# Controlboard.net
KiCad netlist of a schematic drawn in EAGLE
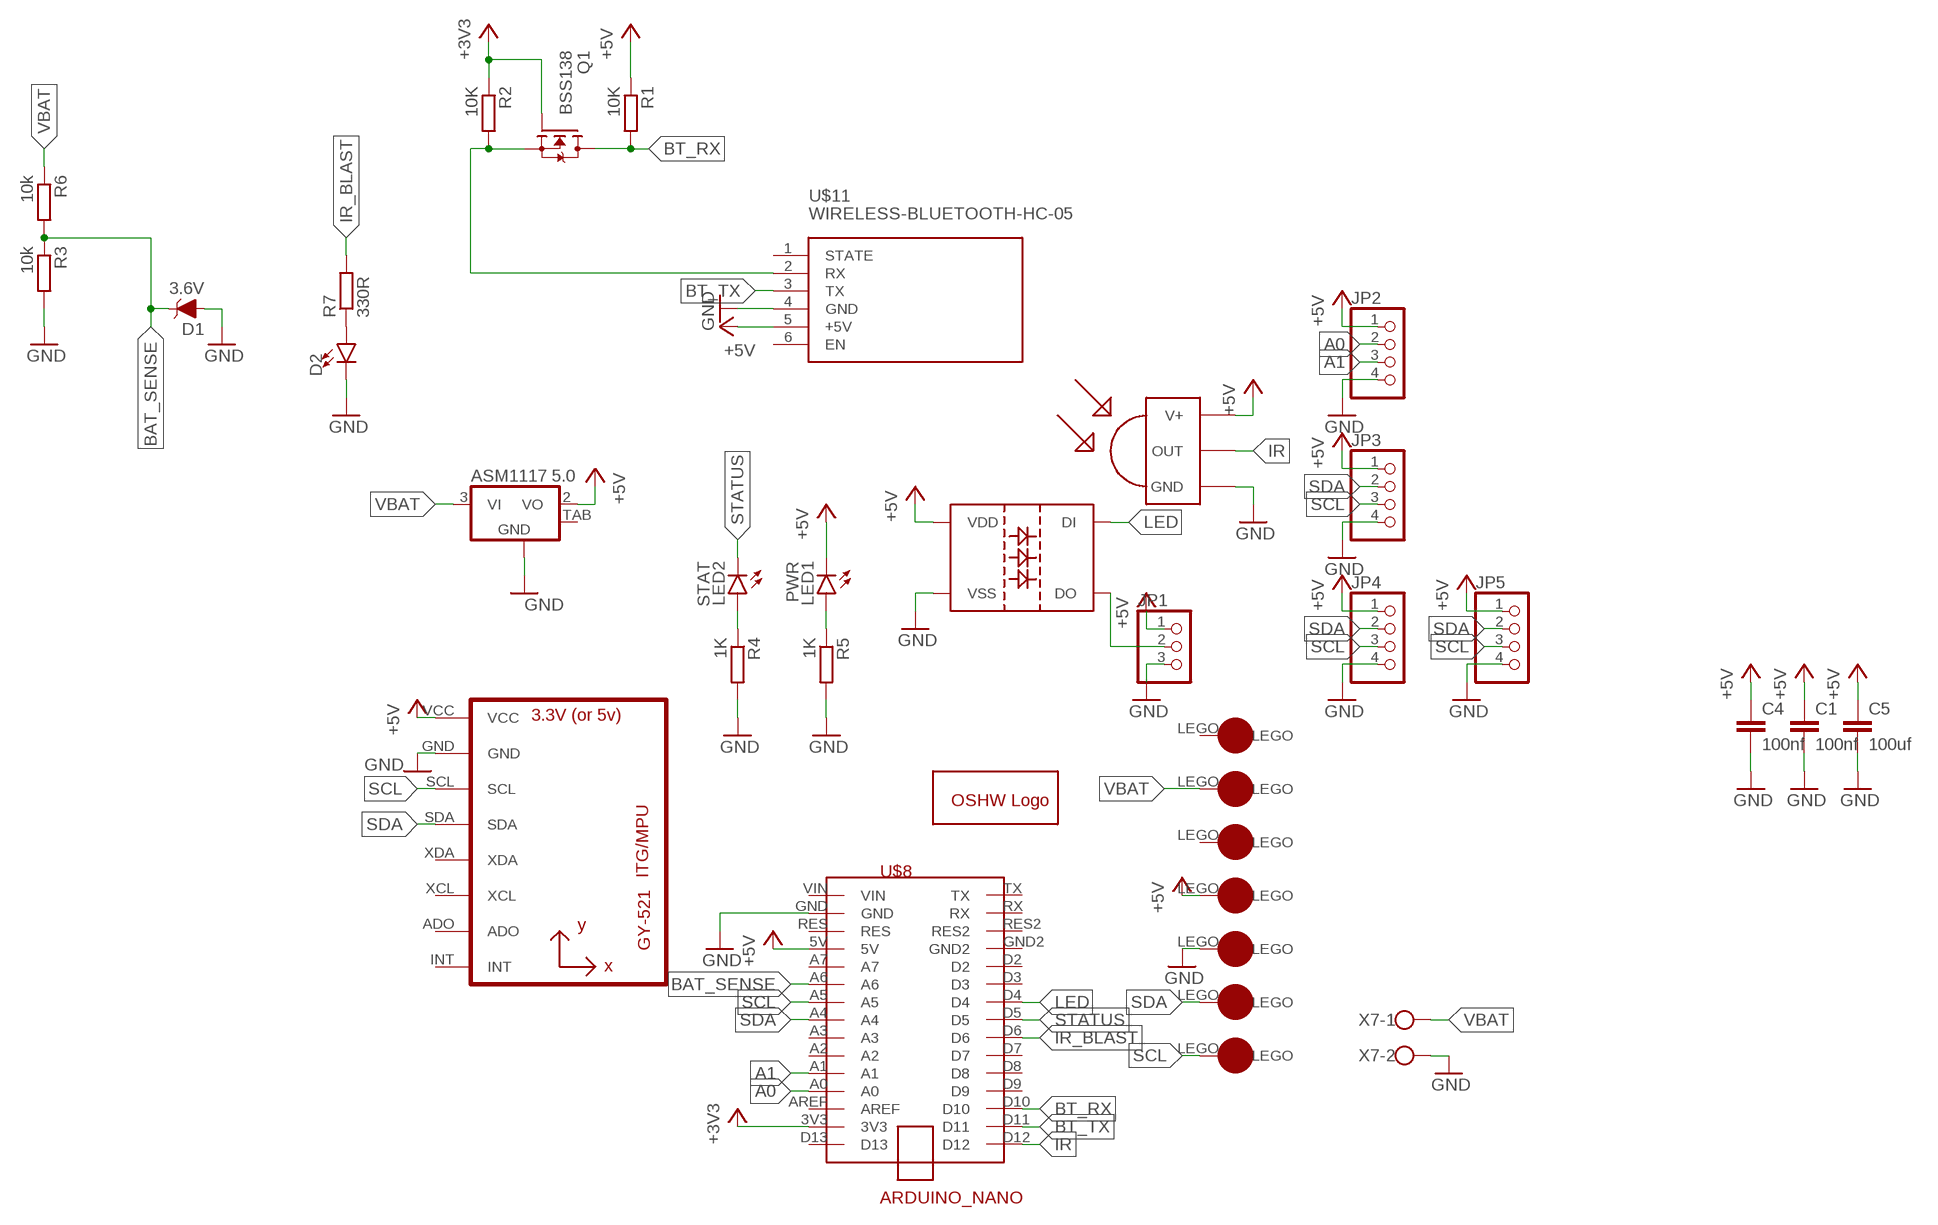
[diagram p0: schematic, sheet 1]

(export (version "E")
  (design (tool "Eeschema 10.0.6"))
  (components
    (comp (ref "C1")
      (value "100nf")
      (footprint "eagle-import:C1206")
      (libsource (lib "eagle-import") (part "C-EUC1206"))
    )
    (comp (ref "C4")
      (value "100nf")
      (footprint "eagle-import:C1206")
      (libsource (lib "eagle-import") (part "C-EUC1206"))
    )
    (comp (ref "C5")
      (value "100uf")
      (footprint "eagle-import:C1206")
      (libsource (lib "eagle-import") (part "C-EUC1206"))
    )
    (comp (ref "D1")
      (value "3.6V")
      (footprint "eagle-import:SOD-323")
      (libsource (lib "eagle-import") (part "DIODE-ZENER-BZT52C3V6S"))
    )
    (comp (ref "D2")
      (value "LED5MM")
      (footprint "eagle-import:LED_5MM")
      (libsource (lib "eagle-import") (part "LED5MM"))
    )
    (comp (ref "JP1")
      (value "PINHD-1X3")
      (footprint "eagle-import:1X03")
      (libsource (lib "eagle-import") (part "PINHD-1X3"))
    )
    (comp (ref "JP2")
      (value "PINHD-1X4")
      (footprint "eagle-import:1X04")
      (libsource (lib "eagle-import") (part "PINHD-1X4"))
    )
    (comp (ref "JP3")
      (value "PINHD-1X4")
      (footprint "eagle-import:1X04")
      (libsource (lib "eagle-import") (part "PINHD-1X4"))
    )
    (comp (ref "JP4")
      (value "PINHD-1X4")
      (footprint "eagle-import:1X04")
      (libsource (lib "eagle-import") (part "PINHD-1X4"))
    )
    (comp (ref "JP5")
      (value "PINHD-1X4")
      (footprint "eagle-import:1X04")
      (libsource (lib "eagle-import") (part "PINHD-1X4"))
    )
    (comp (ref "LED1")
      (value "PWR")
      (footprint "eagle-import:1206")
      (libsource (lib "eagle-import") (part "LEDSMT1206"))
    )
    (comp (ref "LED2")
      (value "STAT")
      (footprint "eagle-import:1206")
      (libsource (lib "eagle-import") (part "LEDSMT1206"))
    )
    (comp (ref "LED3")
      (value "IND")
      (footprint "eagle-import:WS2812B")
      (libsource (lib "eagle-import") (part "WS2812B"))
    )
    (comp (ref "Q1")
      (value "BSS138")
      (footprint "eagle-import:SOT23")
      (fields (field (name "MF") "Fairchild"))
      (libsource (lib "eagle-import") (part "BSS138"))
    )
    (comp (ref "R1")
      (value "10K")
      (footprint "eagle-import:M1206")
      (libsource (lib "eagle-import") (part "R-EU_M1206"))
    )
    (comp (ref "R2")
      (value "10K")
      (footprint "eagle-import:M1206")
      (libsource (lib "eagle-import") (part "R-EU_M1206"))
    )
    (comp (ref "R3")
      (value "10k")
      (footprint "eagle-import:M1206")
      (libsource (lib "eagle-import") (part "R-EU_M1206"))
    )
    (comp (ref "R4")
      (value "1K")
      (footprint "eagle-import:M1206")
      (libsource (lib "eagle-import") (part "R-EU_M1206"))
    )
    (comp (ref "R5")
      (value "1K")
      (footprint "eagle-import:M1206")
      (libsource (lib "eagle-import") (part "R-EU_M1206"))
    )
    (comp (ref "R6")
      (value "10k")
      (footprint "eagle-import:M1206")
      (libsource (lib "eagle-import") (part "R-EU_M1206"))
    )
    (comp (ref "R7")
      (value "330R")
      (footprint "eagle-import:M1206")
      (libsource (lib "eagle-import") (part "R-EU_M1206"))
    )
    (comp (ref "U$1")
      (value "LEGO-1X1")
      (footprint "eagle-import:LEGO-1X1")
      (libsource (lib "eagle-import") (part "LEGO-1X1"))
    )
    (comp (ref "U$2")
      (value "OPENSOURCE")
      (footprint "eagle-import:OSHW_5MM")
      (libsource (lib "eagle-import") (part "OPENSOURCE"))
    )
    (comp (ref "U$3")
      (value "LEGO-1X1")
      (footprint "eagle-import:LEGO-1X1")
      (libsource (lib "eagle-import") (part "LEGO-1X1"))
    )
    (comp (ref "U$4")
      (value "LEGO-1X1")
      (footprint "eagle-import:LEGO-1X1")
      (libsource (lib "eagle-import") (part "LEGO-1X1"))
    )
    (comp (ref "U$5")
      (value "LEGO-1X1")
      (footprint "eagle-import:LEGO-1X1")
      (libsource (lib "eagle-import") (part "LEGO-1X1"))
    )
    (comp (ref "U$6")
      (value "LEGO-1X1")
      (footprint "eagle-import:LEGO-1X1")
      (libsource (lib "eagle-import") (part "LEGO-1X1"))
    )
    (comp (ref "U$7")
      (value "LEGO-1X1")
      (footprint "eagle-import:LEGO-1X1")
      (libsource (lib "eagle-import") (part "LEGO-1X1"))
    )
    (comp (ref "U$8")
      (value "ARDUINO_NANO")
      (footprint "eagle-import:ARDUIN_NANO")
      (libsource (lib "eagle-import") (part "ARDUINO_NANO"))
    )
    (comp (ref "U$9")
      (value "LEGO-1X1")
      (footprint "eagle-import:LEGO-1X1")
      (libsource (lib "eagle-import") (part "LEGO-1X1"))
    )
    (comp (ref "U$10")
      (value "TSOP4838")
      (footprint "eagle-import:TSOP18XX")
      (libsource (lib "eagle-import") (part "TSOP4838"))
    )
    (comp (ref "U$11")
      (value "WIRELESS-BLUETOOTH-HC-05")
      (footprint "eagle-import:WIRELESS-BLUETOOTH-HC-05")
      (libsource (lib "eagle-import") (part "WIRELESS-BLUETOOTH-HC-05"))
    )
    (comp (ref "U$12")
      (value "ASM1117 5.0")
      (footprint "eagle-import:LM1117")
      (libsource (lib "eagle-import") (part "LM1117"))
    )
    (comp (ref "U1")
      (value "MPU-6050MPU6050")
      (footprint "eagle-import:MPU-6050")
      (libsource (lib "eagle-import") (part "MPU-6050MPU6050"))
    )
    (comp (ref "X7")
      (value "W237-102")
      (footprint "eagle-import:W237-102")
      (fields (field (name "MPN") "237-102"))
      (libsource (lib "eagle-import") (part "W237-102"))
    )
  )
  (nets
    (net (code "1") (name "+3V3") (class "Default")
      (node (ref "Q1") (pin "1") (pinfunction "G_1") (pintype "passive"))
      (node (ref "R2") (pin "1") (pinfunction "1_1") (pintype "passive"))
      (node (ref "U$8") (pin "3V3") (pinfunction "3V3_3V3") (pintype "bidirectional"))
    )
    (net (code "2") (name "+5V") (class "Default")
      (node (ref "C1") (pin "1") (pinfunction "1_1") (pintype "passive"))
      (node (ref "C4") (pin "1") (pinfunction "1_1") (pintype "passive"))
      (node (ref "C5") (pin "1") (pinfunction "1_1") (pintype "passive"))
      (node (ref "JP1") (pin "1") (pinfunction "1_1") (pintype "passive"))
      (node (ref "JP2") (pin "1") (pinfunction "1_1") (pintype "passive"))
      (node (ref "JP3") (pin "1") (pinfunction "1_1") (pintype "passive"))
      (node (ref "JP4") (pin "1") (pinfunction "1_1") (pintype "passive"))
      (node (ref "JP5") (pin "1") (pinfunction "1_1") (pintype "passive"))
      (node (ref "LED1") (pin "C") (pinfunction "C_C") (pintype "passive"))
      (node (ref "LED3") (pin "1") (pinfunction "VDD_1") (pintype "bidirectional"))
      (node (ref "R1") (pin "1") (pinfunction "1_1") (pintype "passive"))
      (node (ref "U$10") (pin "VCC") (pinfunction "V+_VCC") (pintype "bidirectional"))
      (node (ref "U$11") (pin "5") (pinfunction "+5V_5") (pintype "power_in"))
      (node (ref "U$12") (pin "2") (pinfunction "VO_2") (pintype "passive"))
      (node (ref "U$5") (pin "LEGO") (pinfunction "LEGO_LEGO") (pintype "bidirectional"))
      (node (ref "U$8") (pin "5V") (pinfunction "5V_5V") (pintype "bidirectional"))
      (node (ref "U1") (pin "VCC") (pinfunction "VCC_VCC") (pintype "bidirectional"))
    )
    (net (code "3") (name "A0") (class "Default")
      (node (ref "JP2") (pin "2") (pinfunction "2_2") (pintype "passive"))
      (node (ref "U$8") (pin "A0") (pinfunction "A0_A0") (pintype "bidirectional"))
    )
    (net (code "4") (name "A1") (class "Default")
      (node (ref "JP2") (pin "3") (pinfunction "3_3") (pintype "passive"))
      (node (ref "U$8") (pin "A1") (pinfunction "A1_A1") (pintype "bidirectional"))
    )
    (net (code "5") (name "BAT_SENSE") (class "Default")
      (node (ref "D1") (pin "C") (pinfunction "C_C") (pintype "passive"))
      (node (ref "R3") (pin "1") (pinfunction "1_1") (pintype "passive"))
      (node (ref "R6") (pin "2") (pinfunction "2_2") (pintype "passive"))
      (node (ref "U$8") (pin "A6") (pinfunction "A6_A6") (pintype "bidirectional"))
    )
    (net (code "6") (name "BT_RX") (class "Default")
      (node (ref "Q1") (pin "3") (pinfunction "D_3") (pintype "passive"))
      (node (ref "R1") (pin "2") (pinfunction "2_2") (pintype "passive"))
      (node (ref "U$8") (pin "D10") (pinfunction "D10_D10") (pintype "bidirectional"))
    )
    (net (code "7") (name "BT_TX") (class "Default")
      (node (ref "U$11") (pin "3") (pinfunction "TX_3") (pintype "bidirectional"))
      (node (ref "U$8") (pin "D11") (pinfunction "D11_D11") (pintype "bidirectional"))
    )
    (net (code "8") (name "GND") (class "Default")
      (node (ref "C1") (pin "2") (pinfunction "2_2") (pintype "passive"))
      (node (ref "C4") (pin "2") (pinfunction "2_2") (pintype "passive"))
      (node (ref "C5") (pin "2") (pinfunction "2_2") (pintype "passive"))
      (node (ref "D1") (pin "A") (pinfunction "A_A") (pintype "passive"))
      (node (ref "D2") (pin "K") (pinfunction "C_K") (pintype "passive"))
      (node (ref "JP1") (pin "3") (pinfunction "3_3") (pintype "passive"))
      (node (ref "JP2") (pin "4") (pinfunction "4_4") (pintype "passive"))
      (node (ref "JP3") (pin "4") (pinfunction "4_4") (pintype "passive"))
      (node (ref "JP4") (pin "4") (pinfunction "4_4") (pintype "passive"))
      (node (ref "JP5") (pin "4") (pinfunction "4_4") (pintype "passive"))
      (node (ref "LED3") (pin "3") (pinfunction "VSS_3") (pintype "bidirectional"))
      (node (ref "R3") (pin "2") (pinfunction "2_2") (pintype "passive"))
      (node (ref "R4") (pin "2") (pinfunction "2_2") (pintype "passive"))
      (node (ref "R5") (pin "2") (pinfunction "2_2") (pintype "passive"))
      (node (ref "U$10") (pin "GND") (pinfunction "GND_GND") (pintype "bidirectional"))
      (node (ref "U$11") (pin "4") (pinfunction "GND_4") (pintype "power_in"))
      (node (ref "U$12") (pin "1") (pinfunction "GND_1") (pintype "passive"))
      (node (ref "U$4") (pin "LEGO") (pinfunction "LEGO_LEGO") (pintype "bidirectional"))
      (node (ref "U$8") (pin "GND") (pinfunction "GND_GND") (pintype "bidirectional"))
      (node (ref "U1") (pin "GND") (pinfunction "GND_GND") (pintype "bidirectional"))
      (node (ref "X7") (pin "2") (pinfunction "KL_2") (pintype "passive"))
    )
    (net (code "9") (name "IR") (class "Default")
      (node (ref "U$10") (pin "OUT") (pinfunction "OUT_OUT") (pintype "bidirectional"))
      (node (ref "U$8") (pin "D12") (pinfunction "D12_D12") (pintype "bidirectional"))
    )
    (net (code "10") (name "IR_BLAST") (class "Default")
      (node (ref "R7") (pin "2") (pinfunction "2_2") (pintype "passive"))
      (node (ref "U$8") (pin "D6") (pinfunction "D6_D6") (pintype "bidirectional"))
    )
    (net (code "11") (name "LED") (class "Default")
      (node (ref "LED3") (pin "4") (pinfunction "DI_4") (pintype "bidirectional"))
      (node (ref "U$8") (pin "D4") (pinfunction "D4_D4") (pintype "bidirectional"))
    )
    (net (code "12") (name "Net-(D2-PadA)") (class "Default")
      (node (ref "D2") (pin "A") (pinfunction "A_A") (pintype "passive"))
      (node (ref "R7") (pin "1") (pinfunction "1_1") (pintype "passive"))
    )
    (net (code "13") (name "Net-(LED1-PadA)") (class "Default")
      (node (ref "LED1") (pin "A") (pinfunction "A_A") (pintype "passive"))
      (node (ref "R5") (pin "1") (pinfunction "1_1") (pintype "passive"))
    )
    (net (code "14") (name "Net-(LED2-PadA)") (class "Default")
      (node (ref "LED2") (pin "A") (pinfunction "A_A") (pintype "passive"))
      (node (ref "R4") (pin "1") (pinfunction "1_1") (pintype "passive"))
    )
    (net (code "15") (name "Net-(LED3-DO)") (class "Default")
      (node (ref "JP1") (pin "2") (pinfunction "2_2") (pintype "passive"))
      (node (ref "LED3") (pin "2") (pinfunction "DO_2") (pintype "bidirectional"))
    )
    (net (code "16") (name "Net-(Q1-S)") (class "Default")
      (node (ref "Q1") (pin "2") (pinfunction "S_2") (pintype "passive"))
      (node (ref "R2") (pin "2") (pinfunction "2_2") (pintype "passive"))
      (node (ref "U$11") (pin "2") (pinfunction "RX_2") (pintype "bidirectional"))
    )
    (net (code "17") (name "SCL") (class "Default")
      (node (ref "JP3") (pin "3") (pinfunction "3_3") (pintype "passive"))
      (node (ref "JP4") (pin "3") (pinfunction "3_3") (pintype "passive"))
      (node (ref "JP5") (pin "3") (pinfunction "3_3") (pintype "passive"))
      (node (ref "U$1") (pin "LEGO") (pinfunction "LEGO_LEGO") (pintype "bidirectional"))
      (node (ref "U$8") (pin "A5") (pinfunction "A5_A5") (pintype "bidirectional"))
      (node (ref "U1") (pin "SCL") (pinfunction "SCL_SCL") (pintype "bidirectional"))
    )
    (net (code "18") (name "SDA") (class "Default")
      (node (ref "JP3") (pin "2") (pinfunction "2_2") (pintype "passive"))
      (node (ref "JP4") (pin "2") (pinfunction "2_2") (pintype "passive"))
      (node (ref "JP5") (pin "2") (pinfunction "2_2") (pintype "passive"))
      (node (ref "U$3") (pin "LEGO") (pinfunction "LEGO_LEGO") (pintype "bidirectional"))
      (node (ref "U$8") (pin "A4") (pinfunction "A4_A4") (pintype "bidirectional"))
      (node (ref "U1") (pin "SDA") (pinfunction "SDA_SDA") (pintype "bidirectional"))
    )
    (net (code "19") (name "STATUS") (class "Default")
      (node (ref "LED2") (pin "C") (pinfunction "C_C") (pintype "passive"))
      (node (ref "U$8") (pin "D5") (pinfunction "D5_D5") (pintype "bidirectional"))
    )
    (net (code "20") (name "VBAT") (class "Default")
      (node (ref "R6") (pin "1") (pinfunction "1_1") (pintype "passive"))
      (node (ref "U$12") (pin "3") (pinfunction "VI_3") (pintype "input"))
      (node (ref "U$7") (pin "LEGO") (pinfunction "LEGO_LEGO") (pintype "bidirectional"))
      (node (ref "X7") (pin "1") (pinfunction "KL_1") (pintype "passive"))
    )
    (net (code "21") (name "unconnected-(U$6-PadLEGO)") (class "Default")
      (node (ref "U$6") (pin "LEGO") (pinfunction "LEGO_LEGO") (pintype "bidirectional"))
    )
    (net (code "22") (name "unconnected-(U$8-PadA2)") (class "Default")
      (node (ref "U$8") (pin "A2") (pinfunction "A2_A2") (pintype "bidirectional"))
    )
    (net (code "23") (name "unconnected-(U$8-PadA3)") (class "Default")
      (node (ref "U$8") (pin "A3") (pinfunction "A3_A3") (pintype "bidirectional"))
    )
    (net (code "24") (name "unconnected-(U$8-PadA7)") (class "Default")
      (node (ref "U$8") (pin "A7") (pinfunction "A7_A7") (pintype "bidirectional"))
    )
    (net (code "25") (name "unconnected-(U$8-PadAREF)") (class "Default")
      (node (ref "U$8") (pin "AREF") (pinfunction "AREF_AREF") (pintype "bidirectional"))
    )
    (net (code "26") (name "unconnected-(U$8-PadD2)") (class "Default")
      (node (ref "U$8") (pin "D2") (pinfunction "D2_D2") (pintype "bidirectional"))
    )
    (net (code "27") (name "unconnected-(U$8-PadD3)") (class "Default")
      (node (ref "U$8") (pin "D3") (pinfunction "D3_D3") (pintype "bidirectional"))
    )
    (net (code "28") (name "unconnected-(U$8-PadD7)") (class "Default")
      (node (ref "U$8") (pin "D7") (pinfunction "D7_D7") (pintype "bidirectional"))
    )
    (net (code "29") (name "unconnected-(U$8-PadD8)") (class "Default")
      (node (ref "U$8") (pin "D8") (pinfunction "D8_D8") (pintype "bidirectional"))
    )
    (net (code "30") (name "unconnected-(U$8-PadD9)") (class "Default")
      (node (ref "U$8") (pin "D9") (pinfunction "D9_D9") (pintype "bidirectional"))
    )
    (net (code "31") (name "unconnected-(U$8-PadD13)") (class "Default")
      (node (ref "U$8") (pin "D13") (pinfunction "D13_D13") (pintype "bidirectional"))
    )
    (net (code "32") (name "unconnected-(U$8-PadGND2)") (class "Default")
      (node (ref "U$8") (pin "GND2") (pinfunction "GND2_GND2") (pintype "bidirectional"))
    )
    (net (code "33") (name "unconnected-(U$8-PadRES)") (class "Default")
      (node (ref "U$8") (pin "RES") (pinfunction "RES_RES") (pintype "bidirectional"))
    )
    (net (code "34") (name "unconnected-(U$8-PadRES2)") (class "Default")
      (node (ref "U$8") (pin "RES2") (pinfunction "RES2_RES2") (pintype "bidirectional"))
    )
    (net (code "35") (name "unconnected-(U$8-PadRX)") (class "Default")
      (node (ref "U$8") (pin "RX") (pinfunction "RX_RX") (pintype "bidirectional"))
    )
    (net (code "36") (name "unconnected-(U$8-PadTX)") (class "Default")
      (node (ref "U$8") (pin "TX") (pinfunction "TX_TX") (pintype "bidirectional"))
    )
    (net (code "37") (name "unconnected-(U$8-PadVIN)") (class "Default")
      (node (ref "U$8") (pin "VIN") (pinfunction "VIN_VIN") (pintype "bidirectional"))
    )
    (net (code "38") (name "unconnected-(U$9-PadLEGO)") (class "Default")
      (node (ref "U$9") (pin "LEGO") (pinfunction "LEGO_LEGO") (pintype "bidirectional"))
    )
    (net (code "39") (name "unconnected-(U$11-EN-Pad6)") (class "Default")
      (node (ref "U$11") (pin "6") (pinfunction "EN_6") (pintype "bidirectional"))
    )
    (net (code "40") (name "unconnected-(U$11-STATE-Pad1)") (class "Default")
      (node (ref "U$11") (pin "1") (pinfunction "STATE_1") (pintype "bidirectional"))
    )
    (net (code "41") (name "unconnected-(U$12-OUT-PadTAB)") (class "Default")
      (node (ref "U$12") (pin "TAB") (pinfunction "OUT_TAB") (pintype "passive"))
    )
    (net (code "42") (name "unconnected-(U1-PadADO)") (class "Default")
      (node (ref "U1") (pin "ADO") (pinfunction "ADO_ADO") (pintype "bidirectional"))
    )
    (net (code "43") (name "unconnected-(U1-PadINT)") (class "Default")
      (node (ref "U1") (pin "INT") (pinfunction "INT_INT") (pintype "bidirectional"))
    )
    (net (code "44") (name "unconnected-(U1-PadXCL)") (class "Default")
      (node (ref "U1") (pin "XCL") (pinfunction "XCL_XCL") (pintype "bidirectional"))
    )
    (net (code "45") (name "unconnected-(U1-PadXDA)") (class "Default")
      (node (ref "U1") (pin "XDA") (pinfunction "XDA_XDA") (pintype "bidirectional"))
    )
  )
)
